# irs-v3.net
KiCad netlist of a schematic drawn in EAGLE
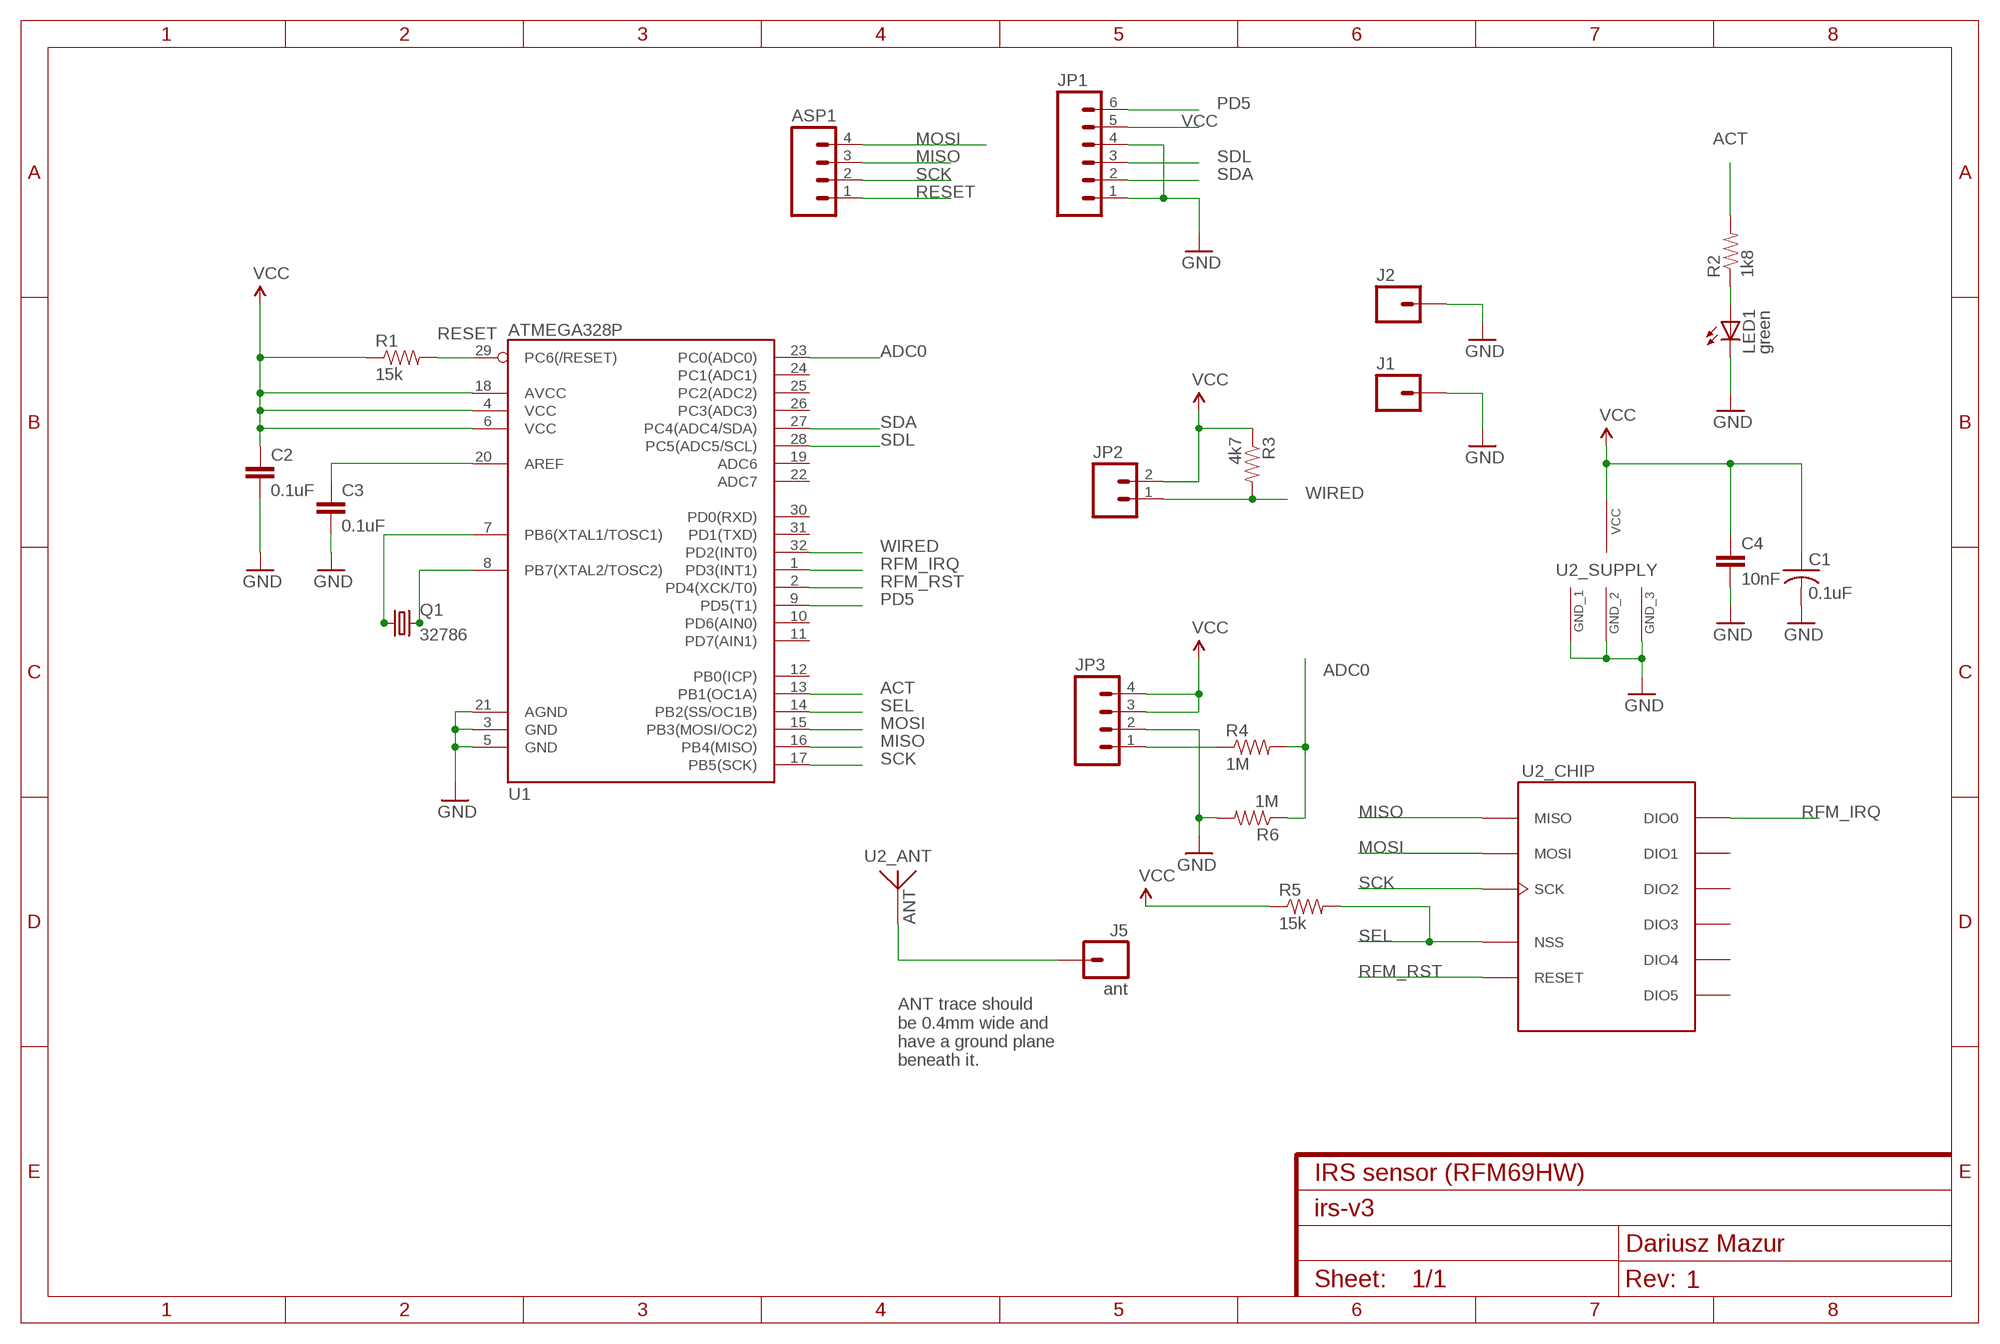
[diagram p0: schematic, sheet 1]

(export (version "E")
  (design (tool "Eeschema 10.0.6"))
  (components
    (comp (ref "ASP1")
      (value "M04NO_SILK_ALL_ROUND")
      (footprint "eagle-import:1X04_NO_SILK_ALL_ROUND")
      (libsource (lib "eagle-import") (part "M04NO_SILK_ALL_ROUND"))
    )
    (comp (ref "C1")
      (value "0.1uF")
      (footprint "eagle-import:C0603")
      (libsource (lib "eagle-import") (part "C-USC0603"))
    )
    (comp (ref "C2")
      (value "0.1uF")
      (footprint "eagle-import:0603-CAP")
      (libsource (lib "eagle-import") (part "0.1UF-25V(+80/-20%)(0603)"))
    )
    (comp (ref "C3")
      (value "0.1uF")
      (footprint "eagle-import:0603-CAP")
      (libsource (lib "eagle-import") (part "0.1UF-25V(+80/-20%)(0603)"))
    )
    (comp (ref "C4")
      (value "10nF")
      (footprint "eagle-import:0603-CAP")
      (libsource (lib "eagle-import") (part "CAP0603-CAP"))
    )
    (comp (ref "J1")
      (value "M01PTH_NO_SILK_YES_STOP")
      (footprint "eagle-import:1X01_NO_SILK")
      (libsource (lib "eagle-import") (part "M01PTH_NO_SILK_YES_STOP"))
    )
    (comp (ref "J2")
      (value "M01PTH_NO_SILK_YES_STOP")
      (footprint "eagle-import:1X01_NO_SILK")
      (libsource (lib "eagle-import") (part "M01PTH_NO_SILK_YES_STOP"))
    )
    (comp (ref "J5")
      (value "ant")
      (footprint "eagle-import:1X01_LONGPAD")
      (libsource (lib "eagle-import") (part "M01PTH_LONGPAD"))
    )
    (comp (ref "JP1")
      (value "M06NO_SILK_FEMALE_PTH")
      (footprint "eagle-import:1X06_NO_SILK")
      (libsource (lib "eagle-import") (part "M06NO_SILK_FEMALE_PTH"))
    )
    (comp (ref "JP2")
      (value "M021X02_NO_SILK")
      (footprint "eagle-import:1X02_NO_SILK")
      (libsource (lib "eagle-import") (part "M021X02_NO_SILK"))
    )
    (comp (ref "JP3")
      (value "M04NO_SILK_ALL_ROUND")
      (footprint "eagle-import:1X04_NO_SILK_ALL_ROUND")
      (libsource (lib "eagle-import") (part "M04NO_SILK_ALL_ROUND"))
    )
    (comp (ref "LED1")
      (value "green")
      (footprint "eagle-import:LED-0603")
      (libsource (lib "eagle-import") (part "LED0603"))
    )
    (comp (ref "Q1")
      (value "32786")
      (footprint "eagle-import:MC-306")
      (fields (field (name "MPN") "MC-306 60.0KHZ  100PPM ,12.5PF"))
      (libsource (lib "eagle-import") (part "MC-306"))
    )
    (comp (ref "R1")
      (value "15k")
      (footprint "eagle-import:0603-RES")
      (libsource (lib "eagle-import") (part "RESISTOR0603-RES"))
    )
    (comp (ref "R2")
      (value "1k8")
      (footprint "eagle-import:0603-RES")
      (libsource (lib "eagle-import") (part "RESISTOR0603-RES"))
    )
    (comp (ref "R3")
      (value "4k7")
      (footprint "eagle-import:0603-RES")
      (libsource (lib "eagle-import") (part "RESISTOR0603-RES"))
    )
    (comp (ref "R4")
      (value "1M")
      (footprint "eagle-import:0603-RES")
      (libsource (lib "eagle-import") (part "RESISTOR0603-RES"))
    )
    (comp (ref "R5")
      (value "15k")
      (footprint "eagle-import:0603-RES")
      (libsource (lib "eagle-import") (part "RESISTOR0603-RES"))
    )
    (comp (ref "R6")
      (value "1M")
      (footprint "eagle-import:0603-RES")
      (libsource (lib "eagle-import") (part "RESISTOR0603-RES"))
    )
    (comp (ref "U1")
      (value "ATMEGA328P")
      (footprint "eagle-import:TQFP32-08")
      (libsource (lib "eagle-import") (part "ATMEGA328_SMT"))
    )
    (comp (ref "U2")
      (value "RFM69HCW-S2")
      (footprint "eagle-import:HOPE-RF-16")
      (libsource (lib "eagle-import") (part "RFM69HCW-S2"))
    )
  )
  (nets
    (net (code "1") (name "/ACT") (class "Default")
      (node (ref "R2") (pin "2") (pinfunction "2_2") (pintype "passive"))
      (node (ref "U1") (pin "13") (pinfunction "PB1(OC1A)_13") (pintype "bidirectional"))
    )
    (net (code "2") (name "/ADC0") (class "Default")
      (node (ref "R4") (pin "2") (pinfunction "2_2") (pintype "passive"))
      (node (ref "R6") (pin "1") (pinfunction "1_1") (pintype "passive"))
      (node (ref "U1") (pin "23") (pinfunction "PC0(ADC0)_23") (pintype "bidirectional"))
    )
    (net (code "3") (name "/MISO") (class "Default")
      (node (ref "ASP1") (pin "3") (pinfunction "3_3") (pintype "passive"))
      (node (ref "U1") (pin "16") (pinfunction "PB4(MISO)_16") (pintype "bidirectional"))
      (node (ref "U2") (pin "MISO") (pinfunction "MISO_MISO") (pintype "input"))
    )
    (net (code "4") (name "/MOSI") (class "Default")
      (node (ref "ASP1") (pin "4") (pinfunction "4_4") (pintype "passive"))
      (node (ref "U1") (pin "15") (pinfunction "PB3(MOSI/OC2)_15") (pintype "bidirectional"))
      (node (ref "U2") (pin "MOSI") (pinfunction "MOSI_MOSI") (pintype "output"))
    )
    (net (code "5") (name "/PD5") (class "Default")
      (node (ref "JP1") (pin "6") (pinfunction "6_6") (pintype "passive"))
      (node (ref "U1") (pin "9") (pinfunction "PD5(T1)_9") (pintype "bidirectional"))
    )
    (net (code "6") (name "/RESET") (class "Default")
      (node (ref "ASP1") (pin "1") (pinfunction "1_1") (pintype "passive"))
      (node (ref "R1") (pin "2") (pinfunction "2_2") (pintype "passive"))
      (node (ref "U1") (pin "29") (pinfunction "PC6(/RESET)_29") (pintype "bidirectional"))
    )
    (net (code "7") (name "/RFM_IRQ") (class "Default")
      (node (ref "U1") (pin "1") (pinfunction "PD3(INT1)_1") (pintype "bidirectional"))
      (node (ref "U2") (pin "DIO0") (pinfunction "DIO0_DIO0") (pintype "bidirectional"))
    )
    (net (code "8") (name "/RFM_RST") (class "Default")
      (node (ref "U1") (pin "2") (pinfunction "PD4(XCK/T0)_2") (pintype "bidirectional"))
      (node (ref "U2") (pin "RESET") (pinfunction "RESET_RESET") (pintype "bidirectional"))
    )
    (net (code "9") (name "/SCK") (class "Default")
      (node (ref "ASP1") (pin "2") (pinfunction "2_2") (pintype "passive"))
      (node (ref "U1") (pin "17") (pinfunction "PB5(SCK)_17") (pintype "bidirectional"))
      (node (ref "U2") (pin "SCK") (pinfunction "SCK_SCK") (pintype "input"))
    )
    (net (code "10") (name "/SDA") (class "Default")
      (node (ref "JP1") (pin "2") (pinfunction "2_2") (pintype "passive"))
      (node (ref "U1") (pin "27") (pinfunction "PC4(ADC4/SDA)_27") (pintype "bidirectional"))
    )
    (net (code "11") (name "/SDL") (class "Default")
      (node (ref "JP1") (pin "3") (pinfunction "3_3") (pintype "passive"))
      (node (ref "U1") (pin "28") (pinfunction "PC5(ADC5/SCL)_28") (pintype "bidirectional"))
    )
    (net (code "12") (name "/SEL") (class "Default")
      (node (ref "R5") (pin "2") (pinfunction "2_2") (pintype "passive"))
      (node (ref "U1") (pin "14") (pinfunction "PB2(SS/OC1B)_14") (pintype "bidirectional"))
      (node (ref "U2") (pin "NSS") (pinfunction "NSS_NSS") (pintype "input"))
    )
    (net (code "13") (name "/WIRED") (class "Default")
      (node (ref "JP2") (pin "1") (pinfunction "1_1") (pintype "passive"))
      (node (ref "R3") (pin "2") (pinfunction "2_2") (pintype "passive"))
      (node (ref "U1") (pin "32") (pinfunction "PD2(INT0)_32") (pintype "bidirectional"))
    )
    (net (code "14") (name "GND") (class "Default")
      (node (ref "C1") (pin "2") (pinfunction "2_2") (pintype "passive"))
      (node (ref "C2") (pin "2") (pinfunction "2_2") (pintype "passive"))
      (node (ref "C3") (pin "2") (pinfunction "2_2") (pintype "passive"))
      (node (ref "C4") (pin "2") (pinfunction "2_2") (pintype "passive"))
      (node (ref "J1") (pin "1") (pinfunction "1_1") (pintype "passive"))
      (node (ref "J2") (pin "1") (pinfunction "1_1") (pintype "passive"))
      (node (ref "JP1") (pin "1") (pinfunction "1_1") (pintype "passive"))
      (node (ref "JP1") (pin "4") (pinfunction "4_4") (pintype "passive"))
      (node (ref "JP3") (pin "2") (pinfunction "2_2") (pintype "passive"))
      (node (ref "LED1") (pin "C") (pinfunction "C_C") (pintype "passive"))
      (node (ref "R6") (pin "2") (pinfunction "2_2") (pintype "passive"))
      (node (ref "U1") (pin "21") (pinfunction "AGND_21") (pintype "bidirectional"))
      (node (ref "U1") (pin "3") (pinfunction "GND_3") (pintype "bidirectional"))
      (node (ref "U1") (pin "5") (pinfunction "GND_5") (pintype "bidirectional"))
      (node (ref "U2") (pin "GND1") (pinfunction "GND_1_GND1") (pintype "power_in"))
      (node (ref "U2") (pin "GND2") (pinfunction "GND_2_GND2") (pintype "power_in"))
      (node (ref "U2") (pin "GND3") (pinfunction "GND_3_GND3") (pintype "power_in"))
    )
    (net (code "15") (name "Net-(J5-Pad1)") (class "Default")
      (node (ref "J5") (pin "1") (pinfunction "1_1") (pintype "passive"))
      (node (ref "U2") (pin "ANT") (pinfunction "ANT_ANT") (pintype "passive"))
    )
    (net (code "16") (name "Net-(JP3-Pad1)") (class "Default")
      (node (ref "JP3") (pin "1") (pinfunction "1_1") (pintype "passive"))
      (node (ref "R4") (pin "1") (pinfunction "1_1") (pintype "passive"))
    )
    (net (code "17") (name "Net-(LED1-PadA)") (class "Default")
      (node (ref "LED1") (pin "A") (pinfunction "A_A") (pintype "passive"))
      (node (ref "R2") (pin "1") (pinfunction "1_1") (pintype "passive"))
    )
    (net (code "18") (name "Net-(Q1-2)") (class "Default")
      (node (ref "Q1") (pin "4") (pinfunction "2_4") (pintype "passive"))
      (node (ref "U1") (pin "8") (pinfunction "PB7(XTAL2/TOSC2)_8") (pintype "bidirectional"))
    )
    (net (code "19") (name "Net-(U1-AREF)") (class "Default")
      (node (ref "C3") (pin "1") (pinfunction "1_1") (pintype "passive"))
      (node (ref "U1") (pin "20") (pinfunction "AREF_20") (pintype "bidirectional"))
    )
    (net (code "20") (name "Net-(U1-PB6(XTAL1{slash}TOSC1))") (class "Default")
      (node (ref "Q1") (pin "1") (pinfunction "1_1") (pintype "passive"))
      (node (ref "U1") (pin "7") (pinfunction "PB6(XTAL1/TOSC1)_7") (pintype "bidirectional"))
    )
    (net (code "21") (name "VCC") (class "Default")
      (node (ref "C1") (pin "1") (pinfunction "1_1") (pintype "passive"))
      (node (ref "C2") (pin "1") (pinfunction "1_1") (pintype "passive"))
      (node (ref "C4") (pin "1") (pinfunction "1_1") (pintype "passive"))
      (node (ref "JP1") (pin "5") (pinfunction "5_5") (pintype "passive"))
      (node (ref "JP2") (pin "2") (pinfunction "2_2") (pintype "passive"))
      (node (ref "JP3") (pin "3") (pinfunction "3_3") (pintype "passive"))
      (node (ref "JP3") (pin "4") (pinfunction "4_4") (pintype "passive"))
      (node (ref "R1") (pin "1") (pinfunction "1_1") (pintype "passive"))
      (node (ref "R3") (pin "1") (pinfunction "1_1") (pintype "passive"))
      (node (ref "R5") (pin "1") (pinfunction "1_1") (pintype "passive"))
      (node (ref "U1") (pin "18") (pinfunction "AVCC_18") (pintype "bidirectional"))
      (node (ref "U1") (pin "4") (pinfunction "VCC_4") (pintype "bidirectional"))
      (node (ref "U1") (pin "6") (pinfunction "VCC_6") (pintype "bidirectional"))
      (node (ref "U2") (pin "3.3V") (pinfunction "VCC_3.3V") (pintype "power_in"))
    )
    (net (code "22") (name "unconnected-(U1-ADC6-Pad19)") (class "Default")
      (node (ref "U1") (pin "19") (pinfunction "ADC6_19") (pintype "bidirectional"))
    )
    (net (code "23") (name "unconnected-(U1-ADC7-Pad22)") (class "Default")
      (node (ref "U1") (pin "22") (pinfunction "ADC7_22") (pintype "bidirectional"))
    )
    (net (code "24") (name "unconnected-(U1-PB0(ICP)-Pad12)") (class "Default")
      (node (ref "U1") (pin "12") (pinfunction "PB0(ICP)_12") (pintype "bidirectional"))
    )
    (net (code "25") (name "unconnected-(U1-PC1(ADC1)-Pad24)") (class "Default")
      (node (ref "U1") (pin "24") (pinfunction "PC1(ADC1)_24") (pintype "bidirectional"))
    )
    (net (code "26") (name "unconnected-(U1-PC2(ADC2)-Pad25)") (class "Default")
      (node (ref "U1") (pin "25") (pinfunction "PC2(ADC2)_25") (pintype "bidirectional"))
    )
    (net (code "27") (name "unconnected-(U1-PC3(ADC3)-Pad26)") (class "Default")
      (node (ref "U1") (pin "26") (pinfunction "PC3(ADC3)_26") (pintype "bidirectional"))
    )
    (net (code "28") (name "unconnected-(U1-PD0(RXD)-Pad30)") (class "Default")
      (node (ref "U1") (pin "30") (pinfunction "PD0(RXD)_30") (pintype "bidirectional"))
    )
    (net (code "29") (name "unconnected-(U1-PD1(TXD)-Pad31)") (class "Default")
      (node (ref "U1") (pin "31") (pinfunction "PD1(TXD)_31") (pintype "bidirectional"))
    )
    (net (code "30") (name "unconnected-(U1-PD6(AIN0)-Pad10)") (class "Default")
      (node (ref "U1") (pin "10") (pinfunction "PD6(AIN0)_10") (pintype "bidirectional"))
    )
    (net (code "31") (name "unconnected-(U1-PD7(AIN1)-Pad11)") (class "Default")
      (node (ref "U1") (pin "11") (pinfunction "PD7(AIN1)_11") (pintype "bidirectional"))
    )
    (net (code "32") (name "unconnected-(U2-PadDIO1)") (class "Default")
      (node (ref "U2") (pin "DIO1") (pinfunction "DIO1_DIO1") (pintype "bidirectional"))
    )
    (net (code "33") (name "unconnected-(U2-PadDIO2)") (class "Default")
      (node (ref "U2") (pin "DIO2") (pinfunction "DIO2_DIO2") (pintype "bidirectional"))
    )
    (net (code "34") (name "unconnected-(U2-PadDIO3)") (class "Default")
      (node (ref "U2") (pin "DIO3") (pinfunction "DIO3_DIO3") (pintype "bidirectional"))
    )
    (net (code "35") (name "unconnected-(U2-PadDIO4)") (class "Default")
      (node (ref "U2") (pin "DIO4") (pinfunction "DIO4_DIO4") (pintype "bidirectional"))
    )
    (net (code "36") (name "unconnected-(U2-PadDIO5)") (class "Default")
      (node (ref "U2") (pin "DIO5") (pinfunction "DIO5_DIO5") (pintype "bidirectional"))
    )
  )
)
